# v2_0_Main.net
KiCad netlist of a schematic drawn in EAGLE
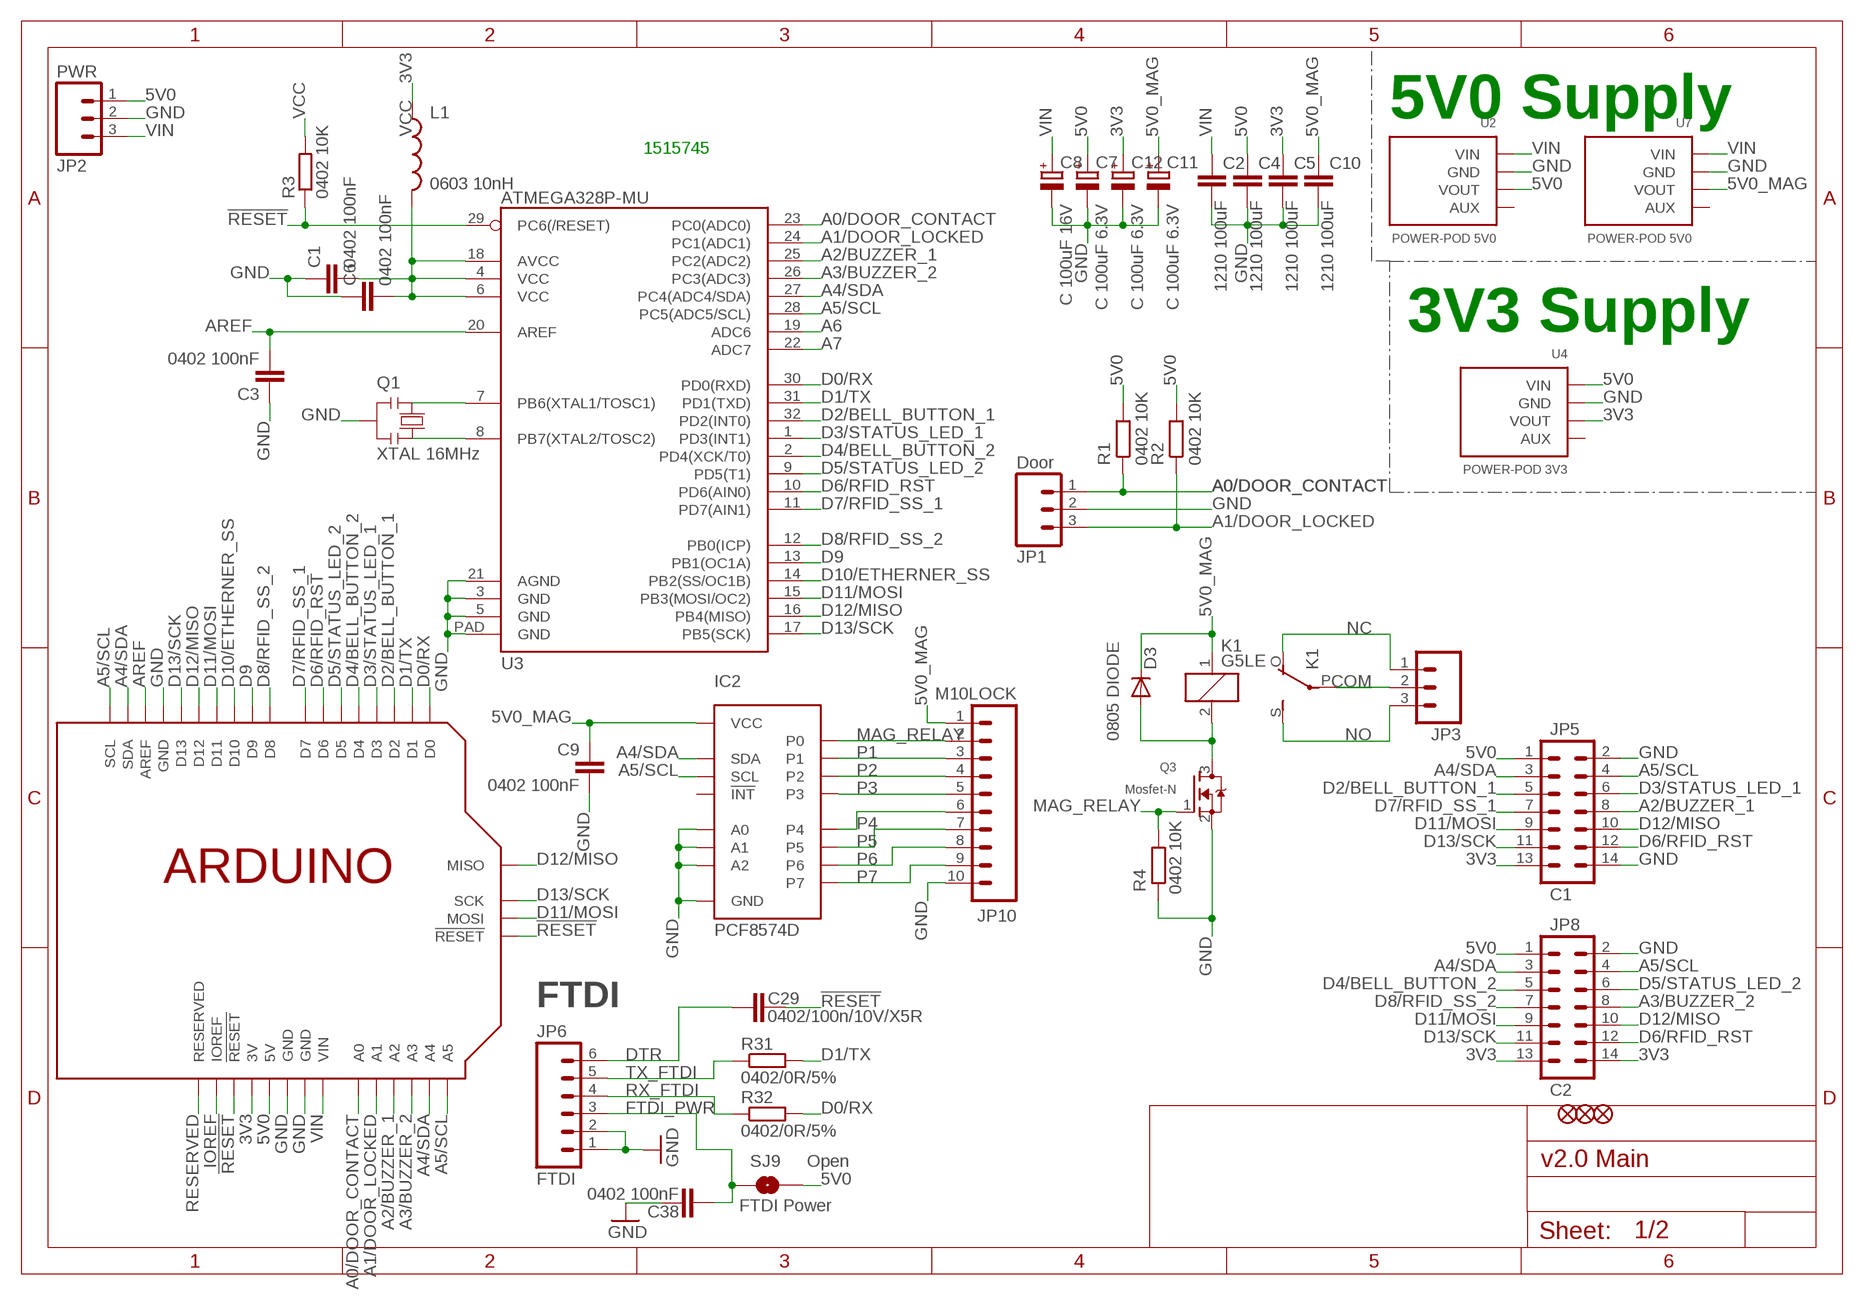
[diagram p0: schematic, sheet 1]
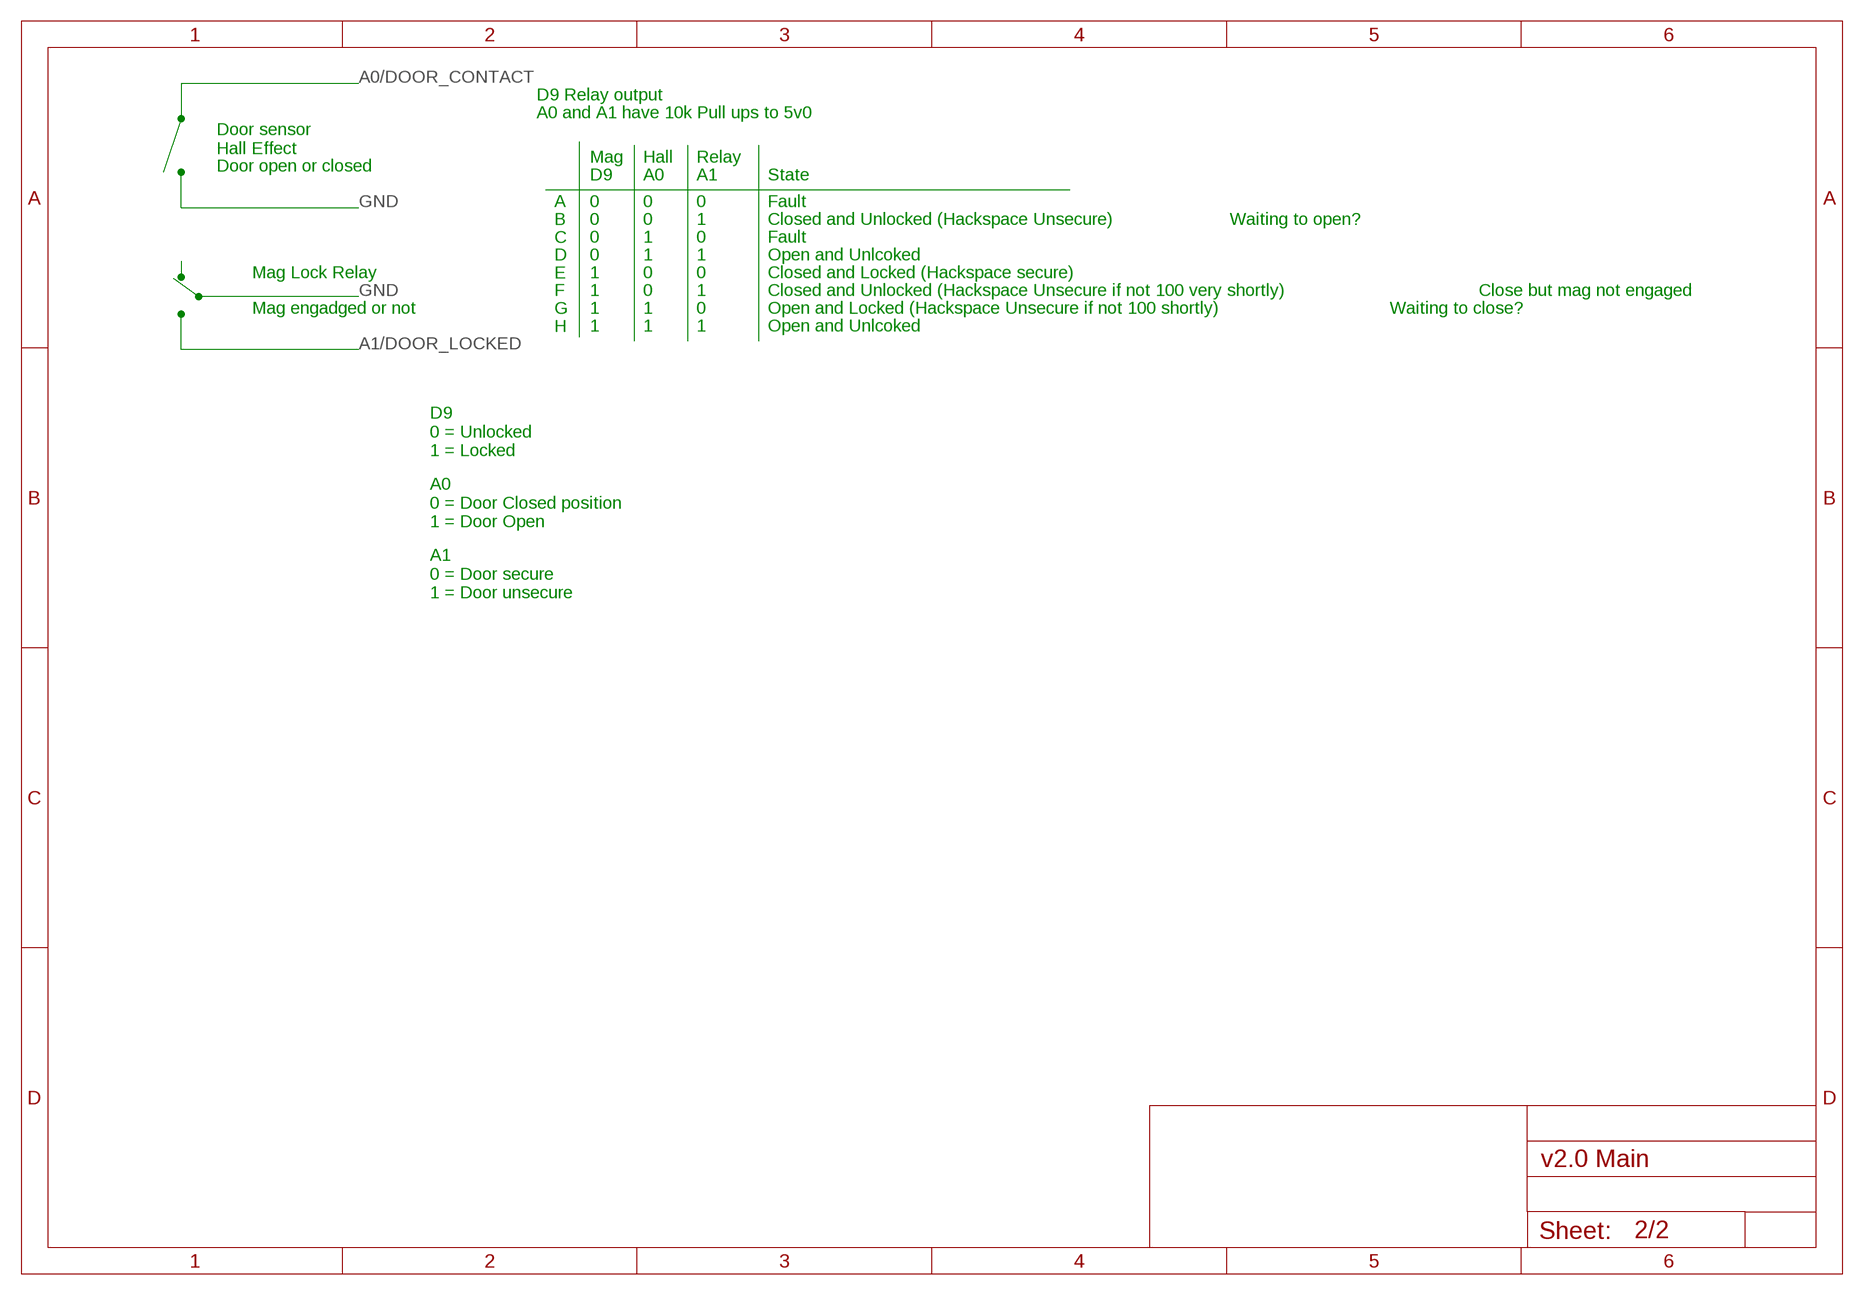
[diagram p1: schematic, sheet 2]

(export (version "E")
  (design (tool "Eeschema 10.0.6"))
  (components
    (comp (ref "C1")
      (value "0402 100nF")
      (footprint "eagle-import:C0402-SMALLER")
      (libsource (lib "eagle-import") (part "C-EUC0402-SMALLER"))
    )
    (comp (ref "C2")
      (value "1210 100uF")
      (footprint "eagle-import:C1210")
      (libsource (lib "eagle-import") (part "C-EUC1210"))
    )
    (comp (ref "C3")
      (value "0402 100nF")
      (footprint "eagle-import:C0402-SMALLER")
      (libsource (lib "eagle-import") (part "C-EUC0402-SMALLER"))
    )
    (comp (ref "C4")
      (value "1210 100uF")
      (footprint "eagle-import:C1210")
      (libsource (lib "eagle-import") (part "C-EUC1210"))
    )
    (comp (ref "C5")
      (value "1210 100uF")
      (footprint "eagle-import:C1210")
      (libsource (lib "eagle-import") (part "C-EUC1210"))
    )
    (comp (ref "C6")
      (value "0402 100nF")
      (footprint "eagle-import:C0402-SMALLER")
      (libsource (lib "eagle-import") (part "C-EUC0402-SMALLER"))
    )
    (comp (ref "C7")
      (value "C 100uF 6.3V")
      (footprint "eagle-import:PANASONIC_C")
      (libsource (lib "eagle-import") (part "CPOL-EUC"))
    )
    (comp (ref "C8")
      (value "C 100uF 16V")
      (footprint "eagle-import:PANASONIC_C")
      (libsource (lib "eagle-import") (part "CPOL-EUC"))
    )
    (comp (ref "C9")
      (value "0402 100nF")
      (footprint "eagle-import:C0402-SMALLER")
      (libsource (lib "eagle-import") (part "C-EUC0402-SMALLER"))
    )
    (comp (ref "C10")
      (value "1210 100uF")
      (footprint "eagle-import:C1210")
      (libsource (lib "eagle-import") (part "C-EUC1210"))
    )
    (comp (ref "C11")
      (value "C 100uF 6.3V")
      (footprint "eagle-import:PANASONIC_C")
      (libsource (lib "eagle-import") (part "CPOL-EUC"))
    )
    (comp (ref "C12")
      (value "C 100uF 6.3V")
      (footprint "eagle-import:PANASONIC_C")
      (libsource (lib "eagle-import") (part "CPOL-EUC"))
    )
    (comp (ref "C29")
      (value "0402/100n/10V/X5R")
      (footprint "eagle-import:C0402-ARDUINO-ROUND")
      (libsource (lib "eagle-import") (part "TiLDA Mk2 Parts_C-EUC0402-ARDUINO-ROUND"))
    )
    (comp (ref "C38")
      (value "0402 100nF")
      (footprint "eagle-import:C0402-SMALLER")
      (libsource (lib "eagle-import") (part "TiLDA Mk2 Parts_C-EUC0402-SMALLER"))
    )
    (comp (ref "D3")
      (value "0805 DIODE")
      (footprint "eagle-import:0805-DIODE")
      (libsource (lib "eagle-import") (part "DIODE-0805"))
    )
    (comp (ref "IC2")
      (value "PCF8574D")
      (footprint "eagle-import:SO16")
      (libsource (lib "eagle-import") (part "PCF8574"))
    )
    (comp (ref "JP1")
      (value "Door")
      (footprint "eagle-import:SCREWTERMINAL-5MM-3")
      (libsource (lib "eagle-import") (part "M03-SCREW-5MM"))
    )
    (comp (ref "JP2")
      (value "PWR")
      (footprint "eagle-import:SCREWTERMINAL-5MM-3")
      (libsource (lib "eagle-import") (part "M03-SCREW-5MM"))
    )
    (comp (ref "JP3")
      (value "M03-SCREW-5MM")
      (footprint "eagle-import:SCREWTERMINAL-5MM-3")
      (libsource (lib "eagle-import") (part "M03-SCREW-5MM"))
    )
    (comp (ref "JP4")
      (value "FIDUCIAL1X2.5-STOP")
      (footprint "eagle-import:FIDUCIAL-1X2.5-STOP")
      (libsource (lib "eagle-import") (part "FIDUCIAL1X2.5-STOP"))
    )
    (comp (ref "JP5")
      (value "C1")
      (footprint "eagle-import:2X7-SHROUDED_LOCK")
      (libsource (lib "eagle-import") (part "M07X2-SHOROUDED_LOCK"))
    )
    (comp (ref "JP6")
      (value "FTDI")
      (footprint "eagle-import:1X06")
      (libsource (lib "eagle-import") (part "M06SIP"))
    )
    (comp (ref "JP7")
      (value "FIDUCIAL1X2.5-STOP")
      (footprint "eagle-import:FIDUCIAL-1X2.5-STOP")
      (libsource (lib "eagle-import") (part "FIDUCIAL1X2.5-STOP"))
    )
    (comp (ref "JP8")
      (value "C2")
      (footprint "eagle-import:2X7-SHROUDED_LOCK")
      (libsource (lib "eagle-import") (part "M07X2-SHOROUDED_LOCK"))
    )
    (comp (ref "JP9")
      (value "FIDUCIAL1X2.5-STOP")
      (footprint "eagle-import:FIDUCIAL-1X2.5-STOP")
      (libsource (lib "eagle-import") (part "FIDUCIAL1X2.5-STOP"))
    )
    (comp (ref "JP10")
      (value "M10LOCK")
      (footprint "eagle-import:1X10_LOCK")
      (libsource (lib "eagle-import") (part "M10LOCK"))
    )
    (comp (ref "K1")
      (value "G5LE")
      (footprint "eagle-import:G5LE-NOSTOP-SMALL")
      (libsource (lib "eagle-import") (part "G5LE-NO_TSOP-SMALL"))
    )
    (comp (ref "L1")
      (value "0603 10nH")
      (footprint "eagle-import:C0603K-SMALL")
      (libsource (lib "eagle-import") (part "INDUCTOR0603K-SMALL"))
    )
    (comp (ref "Q1")
      (value "XTAL 16MHz")
      (footprint "eagle-import:RESONATOR")
      (libsource (lib "eagle-import") (part "RESONATORMU"))
    )
    (comp (ref "Q3")
      (value "Mosfet-N")
      (footprint "eagle-import:SOT23-3")
      (libsource (lib "eagle-import") (part "MOSFET-N-SOT23-SPARK"))
    )
    (comp (ref "R1")
      (value "0402 10K")
      (footprint "eagle-import:R0402-SMALLER")
      (libsource (lib "eagle-import") (part "R-EU_R0402-SMALLER"))
    )
    (comp (ref "R2")
      (value "0402 10K")
      (footprint "eagle-import:R0402-SMALLER")
      (libsource (lib "eagle-import") (part "R-EU_R0402-SMALLER"))
    )
    (comp (ref "R3")
      (value "0402 10K")
      (footprint "eagle-import:R0402-SMALLER")
      (libsource (lib "eagle-import") (part "R-EU_R0402-SMALLER"))
    )
    (comp (ref "R4")
      (value "0402 10K")
      (footprint "eagle-import:R0402-SMALLER")
      (libsource (lib "eagle-import") (part "R-EU_R0402-SMALLER"))
    )
    (comp (ref "R31")
      (value "0402/0R/5%")
      (footprint "eagle-import:R0402-ARDUINO-ROUND")
      (libsource (lib "eagle-import") (part "TiLDA Mk2 Parts_R-EU_R0402-ARDUINO-ROUND"))
    )
    (comp (ref "R32")
      (value "0402/0R/5%")
      (footprint "eagle-import:R0402-ARDUINO-ROUND")
      (libsource (lib "eagle-import") (part "TiLDA Mk2 Parts_R-EU_R0402-ARDUINO-ROUND"))
    )
    (comp (ref "SJ9")
      (value "FTDI Power")
      (footprint "eagle-import:SJ_2S-TRACE")
      (libsource (lib "eagle-import") (part "SOLDERJUMPERTRACE"))
    )
    (comp (ref "U1")
      (value "ARDUINOSPI-REFRENCE")
      (footprint "eagle-import:ARDUINOR3-LWKTXT-REF-SPI")
      (libsource (lib "eagle-import") (part "ARDUINOSPI-REFRENCE"))
    )
    (comp (ref "U2")
      (value "POWER-POD 5V0")
      (footprint "eagle-import:POWER-POD-LANDING")
      (libsource (lib "eagle-import") (part "POWER-POD"))
    )
    (comp (ref "U3")
      (value "ATMEGA328P-MU")
      (footprint "eagle-import:MLF32-SHORT-CREAM")
      (libsource (lib "eagle-import") (part "ATMEGA328-MLF-SHORT"))
    )
    (comp (ref "U4")
      (value "POWER-POD 3V3")
      (footprint "eagle-import:POWER-POD-LANDING")
      (libsource (lib "eagle-import") (part "POWER-POD"))
    )
    (comp (ref "U7")
      (value "POWER-POD 5V0")
      (footprint "eagle-import:POWER-POD-LANDING")
      (libsource (lib "eagle-import") (part "POWER-POD"))
    )
  )
  (nets
    (net (code "1") (name "3V3") (class "Default")
      (node (ref "C12") (pin "+") (pinfunction "+_+") (pintype "passive"))
      (node (ref "C5") (pin "1") (pinfunction "1_1") (pintype "passive"))
      (node (ref "JP5") (pin "13") (pinfunction "13_13") (pintype "passive"))
      (node (ref "JP8") (pin "13") (pinfunction "13_13") (pintype "passive"))
      (node (ref "JP8") (pin "14") (pinfunction "14_14") (pintype "passive"))
      (node (ref "L1") (pin "1") (pinfunction "1_1") (pintype "passive"))
      (node (ref "U1") (pin "3V") (pinfunction "3V_3V") (pintype "power_in"))
      (node (ref "U4") (pin "3") (pinfunction "VOUT_3") (pintype "bidirectional"))
    )
    (net (code "2") (name "5V0") (class "Default")
      (node (ref "C4") (pin "1") (pinfunction "1_1") (pintype "passive"))
      (node (ref "C7") (pin "+") (pinfunction "+_+") (pintype "passive"))
      (node (ref "JP2") (pin "1") (pinfunction "1_1") (pintype "passive"))
      (node (ref "JP5") (pin "1") (pinfunction "1_1") (pintype "passive"))
      (node (ref "JP8") (pin "1") (pinfunction "1_1") (pintype "passive"))
      (node (ref "R1") (pin "2") (pinfunction "2_2") (pintype "passive"))
      (node (ref "R2") (pin "2") (pinfunction "2_2") (pintype "passive"))
      (node (ref "SJ9") (pin "2") (pinfunction "2_2") (pintype "passive"))
      (node (ref "U1") (pin "5V") (pinfunction "5V_5V") (pintype "power_in"))
      (node (ref "U1") (pin "5V@ISP") (pinfunction "5V_5V@ISP") (pintype "power_in"))
      (node (ref "U2") (pin "3") (pinfunction "VOUT_3") (pintype "bidirectional"))
      (node (ref "U4") (pin "1") (pinfunction "VIN_1") (pintype "bidirectional"))
    )
    (net (code "3") (name "5V0_MAG") (class "Default")
      (node (ref "C10") (pin "1") (pinfunction "1_1") (pintype "passive"))
      (node (ref "C11") (pin "+") (pinfunction "+_+") (pintype "passive"))
      (node (ref "C9") (pin "1") (pinfunction "1_1") (pintype "passive"))
      (node (ref "D3") (pin "C") (pinfunction "C_C") (pintype "passive"))
      (node (ref "IC2") (pin "16") (pinfunction "VCC_16") (pintype "bidirectional"))
      (node (ref "JP10") (pin "1") (pinfunction "1_1") (pintype "passive"))
      (node (ref "K1") (pin "1") (pinfunction "1_1") (pintype "passive"))
      (node (ref "U7") (pin "3") (pinfunction "VOUT_3") (pintype "bidirectional"))
    )
    (net (code "4") (name "A0{slash}DOOR_CONTACT") (class "Default")
      (node (ref "JP1") (pin "1") (pinfunction "1_1") (pintype "passive"))
      (node (ref "R1") (pin "1") (pinfunction "1_1") (pintype "passive"))
      (node (ref "U1") (pin "A0") (pinfunction "A0_A0") (pintype "bidirectional"))
      (node (ref "U3") (pin "23") (pinfunction "PC0(ADC0)_23") (pintype "bidirectional"))
    )
    (net (code "5") (name "A1{slash}DOOR_LOCKED") (class "Default")
      (node (ref "JP1") (pin "3") (pinfunction "3_3") (pintype "passive"))
      (node (ref "R2") (pin "1") (pinfunction "1_1") (pintype "passive"))
      (node (ref "U1") (pin "A1") (pinfunction "A1_A1") (pintype "bidirectional"))
      (node (ref "U3") (pin "24") (pinfunction "PC1(ADC1)_24") (pintype "bidirectional"))
    )
    (net (code "6") (name "A2{slash}BUZZER_1") (class "Default")
      (node (ref "JP5") (pin "8") (pinfunction "8_8") (pintype "passive"))
      (node (ref "U1") (pin "A2") (pinfunction "A2_A2") (pintype "bidirectional"))
      (node (ref "U3") (pin "25") (pinfunction "PC2(ADC2)_25") (pintype "bidirectional"))
    )
    (net (code "7") (name "A3{slash}BUZZER_2") (class "Default")
      (node (ref "JP8") (pin "8") (pinfunction "8_8") (pintype "passive"))
      (node (ref "U1") (pin "A3") (pinfunction "A3_A3") (pintype "bidirectional"))
      (node (ref "U3") (pin "26") (pinfunction "PC3(ADC3)_26") (pintype "bidirectional"))
    )
    (net (code "8") (name "A4{slash}SDA") (class "Default")
      (node (ref "IC2") (pin "15") (pinfunction "SDA_15") (pintype "bidirectional"))
      (node (ref "JP5") (pin "3") (pinfunction "3_3") (pintype "passive"))
      (node (ref "JP8") (pin "3") (pinfunction "3_3") (pintype "passive"))
      (node (ref "U1") (pin "A4") (pinfunction "A4_A4") (pintype "bidirectional"))
      (node (ref "U1") (pin "SDA") (pinfunction "SDA_SDA") (pintype "bidirectional"))
      (node (ref "U3") (pin "27") (pinfunction "PC4(ADC4/SDA)_27") (pintype "bidirectional"))
    )
    (net (code "9") (name "A5{slash}SCL") (class "Default")
      (node (ref "IC2") (pin "14") (pinfunction "SCL_14") (pintype "bidirectional"))
      (node (ref "JP5") (pin "4") (pinfunction "4_4") (pintype "passive"))
      (node (ref "JP8") (pin "4") (pinfunction "4_4") (pintype "passive"))
      (node (ref "U1") (pin "A5") (pinfunction "A5_A5") (pintype "bidirectional"))
      (node (ref "U1") (pin "SCL") (pinfunction "SCL_SCL") (pintype "bidirectional"))
      (node (ref "U3") (pin "28") (pinfunction "PC5(ADC5/SCL)_28") (pintype "bidirectional"))
    )
    (net (code "10") (name "A6") (class "Default")
      (node (ref "U3") (pin "19") (pinfunction "ADC6_19") (pintype "bidirectional"))
    )
    (net (code "11") (name "A7") (class "Default")
      (node (ref "U3") (pin "22") (pinfunction "ADC7_22") (pintype "bidirectional"))
    )
    (net (code "12") (name "AREF") (class "Default")
      (node (ref "C3") (pin "2") (pinfunction "2_2") (pintype "passive"))
      (node (ref "U1") (pin "AREF") (pinfunction "AREF_AREF") (pintype "bidirectional"))
      (node (ref "U3") (pin "20") (pinfunction "AREF_20") (pintype "bidirectional"))
    )
    (net (code "13") (name "COM") (class "Default")
      (node (ref "JP3") (pin "2") (pinfunction "2_2") (pintype "passive"))
      (node (ref "K1") (pin "P") (pinfunction "P_P") (pintype "passive"))
    )
    (net (code "14") (name "D0{slash}RX") (class "Default")
      (node (ref "R32") (pin "2") (pinfunction "2_2") (pintype "passive"))
      (node (ref "U1") (pin "D0") (pinfunction "D0_D0") (pintype "bidirectional"))
      (node (ref "U3") (pin "30") (pinfunction "PD0(RXD)_30") (pintype "bidirectional"))
    )
    (net (code "15") (name "D1{slash}TX") (class "Default")
      (node (ref "R31") (pin "2") (pinfunction "2_2") (pintype "passive"))
      (node (ref "U1") (pin "D1") (pinfunction "D1_D1") (pintype "bidirectional"))
      (node (ref "U3") (pin "31") (pinfunction "PD1(TXD)_31") (pintype "bidirectional"))
    )
    (net (code "16") (name "D2{slash}BELL_BUTTON_1") (class "Default")
      (node (ref "JP5") (pin "5") (pinfunction "5_5") (pintype "passive"))
      (node (ref "U1") (pin "D2") (pinfunction "D2_D2") (pintype "bidirectional"))
      (node (ref "U3") (pin "32") (pinfunction "PD2(INT0)_32") (pintype "bidirectional"))
    )
    (net (code "17") (name "D3{slash}STATUS_LED_1") (class "Default")
      (node (ref "JP5") (pin "6") (pinfunction "6_6") (pintype "passive"))
      (node (ref "U1") (pin "D3") (pinfunction "D3_D3") (pintype "bidirectional"))
      (node (ref "U3") (pin "1") (pinfunction "PD3(INT1)_1") (pintype "bidirectional"))
    )
    (net (code "18") (name "D4{slash}BELL_BUTTON_2") (class "Default")
      (node (ref "JP8") (pin "5") (pinfunction "5_5") (pintype "passive"))
      (node (ref "U1") (pin "D4") (pinfunction "D4_D4") (pintype "bidirectional"))
      (node (ref "U3") (pin "2") (pinfunction "PD4(XCK/T0)_2") (pintype "bidirectional"))
    )
    (net (code "19") (name "D5{slash}STATUS_LED_2") (class "Default")
      (node (ref "JP8") (pin "6") (pinfunction "6_6") (pintype "passive"))
      (node (ref "U1") (pin "D5") (pinfunction "D5_D5") (pintype "bidirectional"))
      (node (ref "U3") (pin "9") (pinfunction "PD5(T1)_9") (pintype "bidirectional"))
    )
    (net (code "20") (name "D6{slash}RFID_RST") (class "Default")
      (node (ref "JP5") (pin "12") (pinfunction "12_12") (pintype "passive"))
      (node (ref "JP8") (pin "12") (pinfunction "12_12") (pintype "passive"))
      (node (ref "U1") (pin "D6") (pinfunction "D6_D6") (pintype "bidirectional"))
      (node (ref "U3") (pin "10") (pinfunction "PD6(AIN0)_10") (pintype "bidirectional"))
    )
    (net (code "21") (name "D7{slash}RFID_SS_1") (class "Default")
      (node (ref "JP5") (pin "7") (pinfunction "7_7") (pintype "passive"))
      (node (ref "U1") (pin "D7") (pinfunction "D7_D7") (pintype "bidirectional"))
      (node (ref "U3") (pin "11") (pinfunction "PD7(AIN1)_11") (pintype "bidirectional"))
    )
    (net (code "22") (name "D8{slash}RFID_SS_2") (class "Default")
      (node (ref "JP8") (pin "7") (pinfunction "7_7") (pintype "passive"))
      (node (ref "U1") (pin "D8") (pinfunction "D8_D8") (pintype "bidirectional"))
      (node (ref "U3") (pin "12") (pinfunction "PB0(ICP)_12") (pintype "bidirectional"))
    )
    (net (code "23") (name "D9") (class "Default")
      (node (ref "U1") (pin "D9") (pinfunction "D9_D9") (pintype "bidirectional"))
      (node (ref "U3") (pin "13") (pinfunction "PB1(OC1A)_13") (pintype "bidirectional"))
    )
    (net (code "24") (name "D10{slash}ETHERNER_SS") (class "Default")
      (node (ref "U1") (pin "D10") (pinfunction "D10_D10") (pintype "bidirectional"))
      (node (ref "U3") (pin "14") (pinfunction "PB2(SS/OC1B)_14") (pintype "bidirectional"))
    )
    (net (code "25") (name "D11{slash}MOSI") (class "Default")
      (node (ref "JP5") (pin "9") (pinfunction "9_9") (pintype "passive"))
      (node (ref "JP8") (pin "9") (pinfunction "9_9") (pintype "passive"))
      (node (ref "U1") (pin "D11") (pinfunction "D11_D11") (pintype "bidirectional"))
      (node (ref "U1") (pin "MOSI") (pinfunction "MOSI_MOSI") (pintype "bidirectional"))
      (node (ref "U3") (pin "15") (pinfunction "PB3(MOSI/OC2)_15") (pintype "bidirectional"))
    )
    (net (code "26") (name "D12{slash}MISO") (class "Default")
      (node (ref "JP5") (pin "10") (pinfunction "10_10") (pintype "passive"))
      (node (ref "JP8") (pin "10") (pinfunction "10_10") (pintype "passive"))
      (node (ref "U1") (pin "D12") (pinfunction "D12_D12") (pintype "bidirectional"))
      (node (ref "U1") (pin "MISO") (pinfunction "MISO_MISO") (pintype "bidirectional"))
      (node (ref "U3") (pin "16") (pinfunction "PB4(MISO)_16") (pintype "bidirectional"))
    )
    (net (code "27") (name "D13{slash}SCK") (class "Default")
      (node (ref "JP5") (pin "11") (pinfunction "11_11") (pintype "passive"))
      (node (ref "JP8") (pin "11") (pinfunction "11_11") (pintype "passive"))
      (node (ref "U1") (pin "D13") (pinfunction "D13_D13") (pintype "bidirectional"))
      (node (ref "U1") (pin "SCK") (pinfunction "SCK_SCK") (pintype "bidirectional"))
      (node (ref "U3") (pin "17") (pinfunction "PB5(SCK)_17") (pintype "bidirectional"))
    )
    (net (code "28") (name "DTR") (class "Default")
      (node (ref "C29") (pin "2") (pinfunction "2_2") (pintype "passive"))
      (node (ref "JP6") (pin "6") (pinfunction "6_6") (pintype "passive"))
    )
    (net (code "29") (name "FTDI_PWR") (class "Default")
      (node (ref "C38") (pin "2") (pinfunction "2_2") (pintype "passive"))
      (node (ref "JP6") (pin "3") (pinfunction "3_3") (pintype "passive"))
      (node (ref "SJ9") (pin "1") (pinfunction "1_1") (pintype "passive"))
    )
    (net (code "30") (name "GND") (class "Default")
      (node (ref "C1") (pin "1") (pinfunction "1_1") (pintype "passive"))
      (node (ref "C10") (pin "2") (pinfunction "2_2") (pintype "passive"))
      (node (ref "C11") (pin "-") (pinfunction "-_-") (pintype "passive"))
      (node (ref "C12") (pin "-") (pinfunction "-_-") (pintype "passive"))
      (node (ref "C2") (pin "2") (pinfunction "2_2") (pintype "passive"))
      (node (ref "C3") (pin "1") (pinfunction "1_1") (pintype "passive"))
      (node (ref "C38") (pin "1") (pinfunction "1_1") (pintype "passive"))
      (node (ref "C4") (pin "2") (pinfunction "2_2") (pintype "passive"))
      (node (ref "C5") (pin "2") (pinfunction "2_2") (pintype "passive"))
      (node (ref "C6") (pin "1") (pinfunction "1_1") (pintype "passive"))
      (node (ref "C7") (pin "-") (pinfunction "-_-") (pintype "passive"))
      (node (ref "C8") (pin "-") (pinfunction "-_-") (pintype "passive"))
      (node (ref "C9") (pin "2") (pinfunction "2_2") (pintype "passive"))
      (node (ref "IC2") (pin "1") (pinfunction "A0_1") (pintype "bidirectional"))
      (node (ref "IC2") (pin "2") (pinfunction "A1_2") (pintype "bidirectional"))
      (node (ref "IC2") (pin "3") (pinfunction "A2_3") (pintype "bidirectional"))
      (node (ref "IC2") (pin "8") (pinfunction "GND_8") (pintype "bidirectional"))
      (node (ref "JP1") (pin "2") (pinfunction "2_2") (pintype "passive"))
      (node (ref "JP10") (pin "10") (pinfunction "10_10") (pintype "passive"))
      (node (ref "JP2") (pin "2") (pinfunction "2_2") (pintype "passive"))
      (node (ref "JP5") (pin "14") (pinfunction "14_14") (pintype "passive"))
      (node (ref "JP5") (pin "2") (pinfunction "2_2") (pintype "passive"))
      (node (ref "JP6") (pin "1") (pinfunction "1_1") (pintype "passive"))
      (node (ref "JP6") (pin "2") (pinfunction "2_2") (pintype "passive"))
      (node (ref "JP8") (pin "2") (pinfunction "2_2") (pintype "passive"))
      (node (ref "Q1") (pin "2") (pinfunction "2_2") (pintype "passive"))
      (node (ref "Q3") (pin "2") (pinfunction "S_2") (pintype "bidirectional"))
      (node (ref "R4") (pin "1") (pinfunction "1_1") (pintype "passive"))
      (node (ref "U1") (pin "GND@1") (pinfunction "GND_GND@1") (pintype "power_in"))
      (node (ref "U1") (pin "GND@2") (pinfunction "GND_GND@2") (pintype "power_in"))
      (node (ref "U1") (pin "GND@3") (pinfunction "GND_GND@3") (pintype "power_in"))
      (node (ref "U1") (pin "GND@ISP") (pinfunction "GND_GND@ISP") (pintype "power_in"))
      (node (ref "U2") (pin "2") (pinfunction "GND_2") (pintype "bidirectional"))
      (node (ref "U3") (pin "21") (pinfunction "AGND_21") (pintype "bidirectional"))
      (node (ref "U3") (pin "3") (pinfunction "GND_3") (pintype "bidirectional"))
      (node (ref "U3") (pin "5") (pinfunction "GND_5") (pintype "bidirectional"))
      (node (ref "U3") (pin "PAD") (pinfunction "GND_PAD") (pintype "bidirectional"))
      (node (ref "U4") (pin "2") (pinfunction "GND_2") (pintype "bidirectional"))
      (node (ref "U7") (pin "2") (pinfunction "GND_2") (pintype "bidirectional"))
    )
    (net (code "31") (name "IOREF") (class "Default")
      (node (ref "U1") (pin "IOREF") (pinfunction "IOREF_IOREF") (pintype "output"))
    )
    (net (code "32") (name "MAG_RELAY") (class "Default")
      (node (ref "IC2") (pin "4") (pinfunction "P0_4") (pintype "bidirectional"))
      (node (ref "JP10") (pin "2") (pinfunction "2_2") (pintype "passive"))
      (node (ref "Q3") (pin "1") (pinfunction "G_1") (pintype "bidirectional"))
      (node (ref "R4") (pin "2") (pinfunction "2_2") (pintype "passive"))
    )
    (net (code "34") (name "NC") (class "Default")
      (node (ref "JP3") (pin "1") (pinfunction "1_1") (pintype "passive"))
      (node (ref "K1") (pin "O") (pinfunction "O_O") (pintype "passive"))
    )
    (net (code "35") (name "NO") (class "Default")
      (node (ref "JP3") (pin "3") (pinfunction "3_3") (pintype "passive"))
      (node (ref "K1") (pin "S") (pinfunction "S_S") (pintype "passive"))
    )
    (net (code "36") (name "Net-(Q3-D)") (class "Default")
      (node (ref "D3") (pin "A") (pinfunction "A_A") (pintype "passive"))
      (node (ref "K1") (pin "2") (pinfunction "2_2") (pintype "passive"))
      (node (ref "Q3") (pin "3") (pinfunction "D_3") (pintype "bidirectional"))
    )
    (net (code "37") (name "Net-(U3-PB6(XTAL1{slash}TOSC1))") (class "Default")
      (node (ref "Q1") (pin "1") (pinfunction "1_1") (pintype "passive"))
      (node (ref "U3") (pin "7") (pinfunction "PB6(XTAL1/TOSC1)_7") (pintype "bidirectional"))
    )
    (net (code "38") (name "Net-(U3-PB7(XTAL2{slash}TOSC2))") (class "Default")
      (node (ref "Q1") (pin "3") (pinfunction "3_3") (pintype "passive"))
      (node (ref "U3") (pin "8") (pinfunction "PB7(XTAL2/TOSC2)_8") (pintype "bidirectional"))
    )
    (net (code "39") (name "P1") (class "Default")
      (node (ref "IC2") (pin "5") (pinfunction "P1_5") (pintype "bidirectional"))
      (node (ref "JP10") (pin "3") (pinfunction "3_3") (pintype "passive"))
    )
    (net (code "40") (name "P2") (class "Default")
      (node (ref "IC2") (pin "6") (pinfunction "P2_6") (pintype "bidirectional"))
      (node (ref "JP10") (pin "4") (pinfunction "4_4") (pintype "passive"))
    )
    (net (code "41") (name "P3") (class "Default")
      (node (ref "IC2") (pin "7") (pinfunction "P3_7") (pintype "bidirectional"))
      (node (ref "JP10") (pin "5") (pinfunction "5_5") (pintype "passive"))
    )
    (net (code "42") (name "P4") (class "Default")
      (node (ref "IC2") (pin "9") (pinfunction "P4_9") (pintype "bidirectional"))
      (node (ref "JP10") (pin "6") (pinfunction "6_6") (pintype "passive"))
    )
    (net (code "43") (name "P5") (class "Default")
      (node (ref "IC2") (pin "10") (pinfunction "P5_10") (pintype "bidirectional"))
      (node (ref "JP10") (pin "7") (pinfunction "7_7") (pintype "passive"))
    )
    (net (code "44") (name "P6") (class "Default")
      (node (ref "IC2") (pin "11") (pinfunction "P6_11") (pintype "bidirectional"))
      (node (ref "JP10") (pin "8") (pinfunction "8_8") (pintype "passive"))
    )
    (net (code "45") (name "P7") (class "Default")
      (node (ref "IC2") (pin "12") (pinfunction "P7_12") (pintype "bidirectional"))
      (node (ref "JP10") (pin "9") (pinfunction "9_9") (pintype "passive"))
    )
    (net (code "47") (name "RESERVED") (class "Default")
      (node (ref "U1") (pin "RESERVED") (pinfunction "RESERVED_RESERVED") (pintype "no_connect"))
    )
    (net (code "48") (name "RX_FTDI") (class "Default")
      (node (ref "JP6") (pin "4") (pinfunction "4_4") (pintype "passive"))
      (node (ref "R32") (pin "1") (pinfunction "1_1") (pintype "passive"))
    )
    (net (code "49") (name "TX_FTDI") (class "Default")
      (node (ref "JP6") (pin "5") (pinfunction "5_5") (pintype "passive"))
      (node (ref "R31") (pin "1") (pinfunction "1_1") (pintype "passive"))
    )
    (net (code "50") (name "VCC") (class "Default")
      (node (ref "C1") (pin "2") (pinfunction "2_2") (pintype "passive"))
      (node (ref "C6") (pin "2") (pinfunction "2_2") (pintype "passive"))
      (node (ref "L1") (pin "2") (pinfunction "2_2") (pintype "passive"))
      (node (ref "R3") (pin "2") (pinfunction "2_2") (pintype "passive"))
      (node (ref "U3") (pin "18") (pinfunction "AVCC_18") (pintype "bidirectional"))
      (node (ref "U3") (pin "4") (pinfunction "VCC_4") (pintype "bidirectional"))
      (node (ref "U3") (pin "6") (pinfunction "VCC_6") (pintype "bidirectional"))
    )
    (net (code "51") (name "VIN") (class "Default")
      (node (ref "C2") (pin "1") (pinfunction "1_1") (pintype "passive"))
      (node (ref "C8") (pin "+") (pinfunction "+_+") (pintype "passive"))
      (node (ref "JP2") (pin "3") (pinfunction "3_3") (pintype "passive"))
      (node (ref "U1") (pin "VIN") (pinfunction "VIN_VIN") (pintype "power_in"))
      (node (ref "U2") (pin "1") (pinfunction "VIN_1") (pintype "bidirectional"))
      (node (ref "U7") (pin "1") (pinfunction "VIN_1") (pintype "bidirectional"))
    )
    (net (code "52") (name "unconnected-(IC2-~{INT}-Pad13)") (class "Default")
      (node (ref "IC2") (pin "13") (pinfunction "~{INT}_13") (pintype "bidirectional"))
    )
    (net (code "53") (name "unconnected-(U2-AUX-Pad4)") (class "Default")
      (node (ref "U2") (pin "4") (pinfunction "AUX_4") (pintype "bidirectional"))
    )
    (net (code "54") (name "unconnected-(U4-AUX-Pad4)") (class "Default")
      (node (ref "U4") (pin "4") (pinfunction "AUX_4") (pintype "bidirectional"))
    )
    (net (code "55") (name "unconnected-(U7-AUX-Pad4)") (class "Default")
      (node (ref "U7") (pin "4") (pinfunction "AUX_4") (pintype "bidirectional"))
    )
    (net (code "56") (name "~{RESET}") (class "Default")
      (node (ref "C29") (pin "1") (pinfunction "1_1") (pintype "passive"))
      (node (ref "R3") (pin "1") (pinfunction "1_1") (pintype "passive"))
      (node (ref "U1") (pin "!RESET") (pinfunction "~{RESET}_!RESET") (pintype "bidirectional"))
      (node (ref "U1") (pin "!RESET@ISP") (pinfunction "~{RESET}_!RESET@ISP") (pintype "bidirectional"))
      (node (ref "U3") (pin "29") (pinfunction "PC6(/RESET)_29") (pintype "bidirectional"))
    )
  )
)
